# Debug_Leds.net
KiCad netlist of a schematic drawn in Altium Designer
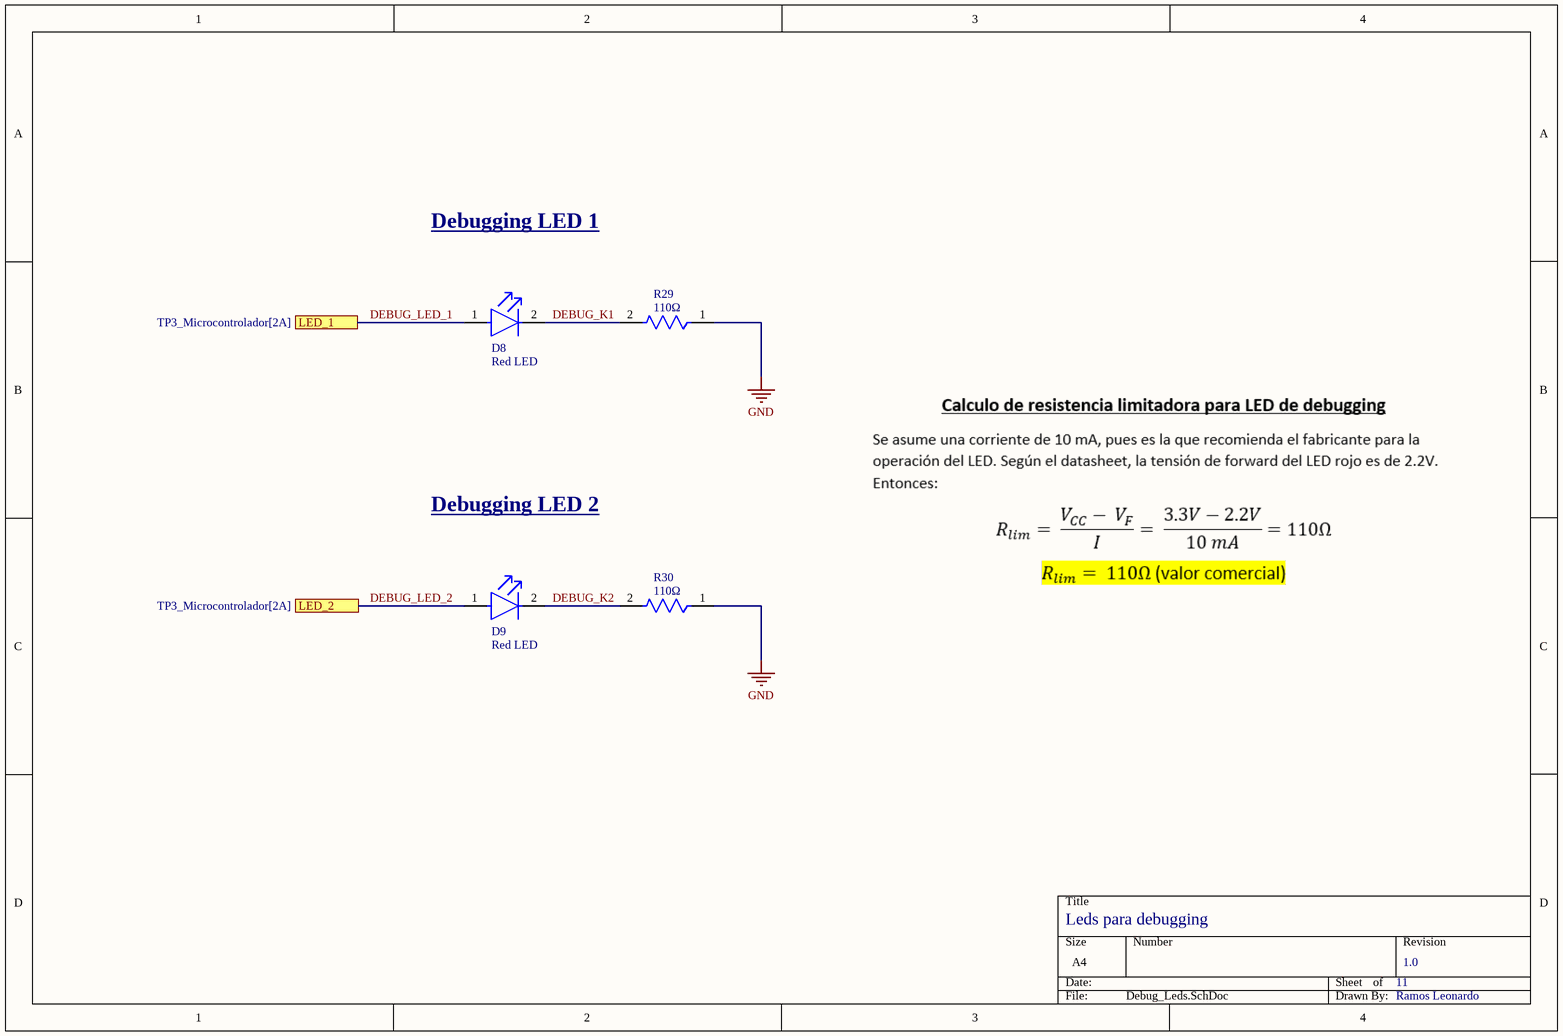
[diagram p0: Debug_Leds.SchDoc]

(export (version "E")
  (design (tool "Eeschema 10.0.6"))
  (components
    (comp (ref "D8")
      (value "Red LED")
      (footprint "FP-SML-LX0805SRC-TR-MFG")
      (description "LED RED CLEAR SMD SML-LX0805SRC-TR")
      (libsource (lib "Altium Content Vault") (part "ab1c01a81903e929fc6c44469aada92"))
    )
    (comp (ref "D9")
      (value "Red LED")
      (footprint "FP-SML-LX0805SRC-TR-MFG")
      (description "LED RED CLEAR SMD SML-LX0805SRC-TR")
      (libsource (lib "Altium Content Vault") (part "ab1c01a81903e929fc6c44469aada92"))
    )
    (comp (ref "R29")
      (value "CRCW08054K70JNEA")
      (footprint "FP-CRCW0805-e3-IPC_B")
      (description "RES Thick Film, 5%, 0.125W, 200ppm/°C, 0805")
      (fields (field (name "TOLERANCE") "5%") (field (name "RESISTANCE") "110Ω"))
      (libsource (lib "Altium Content Vault") (part "1029c3af85768c4190bb7ad29bc67b5"))
    )
    (comp (ref "R30")
      (value "CRCW08054K70JNEA")
      (footprint "FP-CRCW0805-e3-IPC_B")
      (description "RES Thick Film, 5%, 0.125W, 200ppm/°C, 0805")
      (fields (field (name "TOLERANCE") "5%") (field (name "RESISTANCE") "110Ω"))
      (libsource (lib "Altium Content Vault") (part "1029c3af85768c4190bb7ad29bc67b5"))
    )
  )
  (nets
    (net (code "1") (name "/DEBUG_K1") (class "Default")
      (node (ref "D8") (pin "2") (pinfunction "C_2") (pintype "passive"))
      (node (ref "R29") (pin "2") (pinfunction "2_2") (pintype "passive"))
    )
    (net (code "2") (name "/DEBUG_K2") (class "Default")
      (node (ref "D9") (pin "2") (pinfunction "C_2") (pintype "passive"))
      (node (ref "R30") (pin "2") (pinfunction "2_2") (pintype "passive"))
    )
    (net (code "3") (name "/DEBUG_LED_1") (class "Default")
      (node (ref "D8") (pin "1") (pinfunction "A_1") (pintype "passive"))
    )
    (net (code "4") (name "/DEBUG_LED_2") (class "Default")
      (node (ref "D9") (pin "1") (pinfunction "A_1") (pintype "passive"))
    )
    (net (code "5") (name "GND") (class "Default")
      (node (ref "R29") (pin "1") (pinfunction "1_1") (pintype "passive"))
      (node (ref "R30") (pin "1") (pinfunction "1_1") (pintype "passive"))
    )
  )
)
